# QSPI.net
KiCad netlist of a schematic drawn in Altium Designer
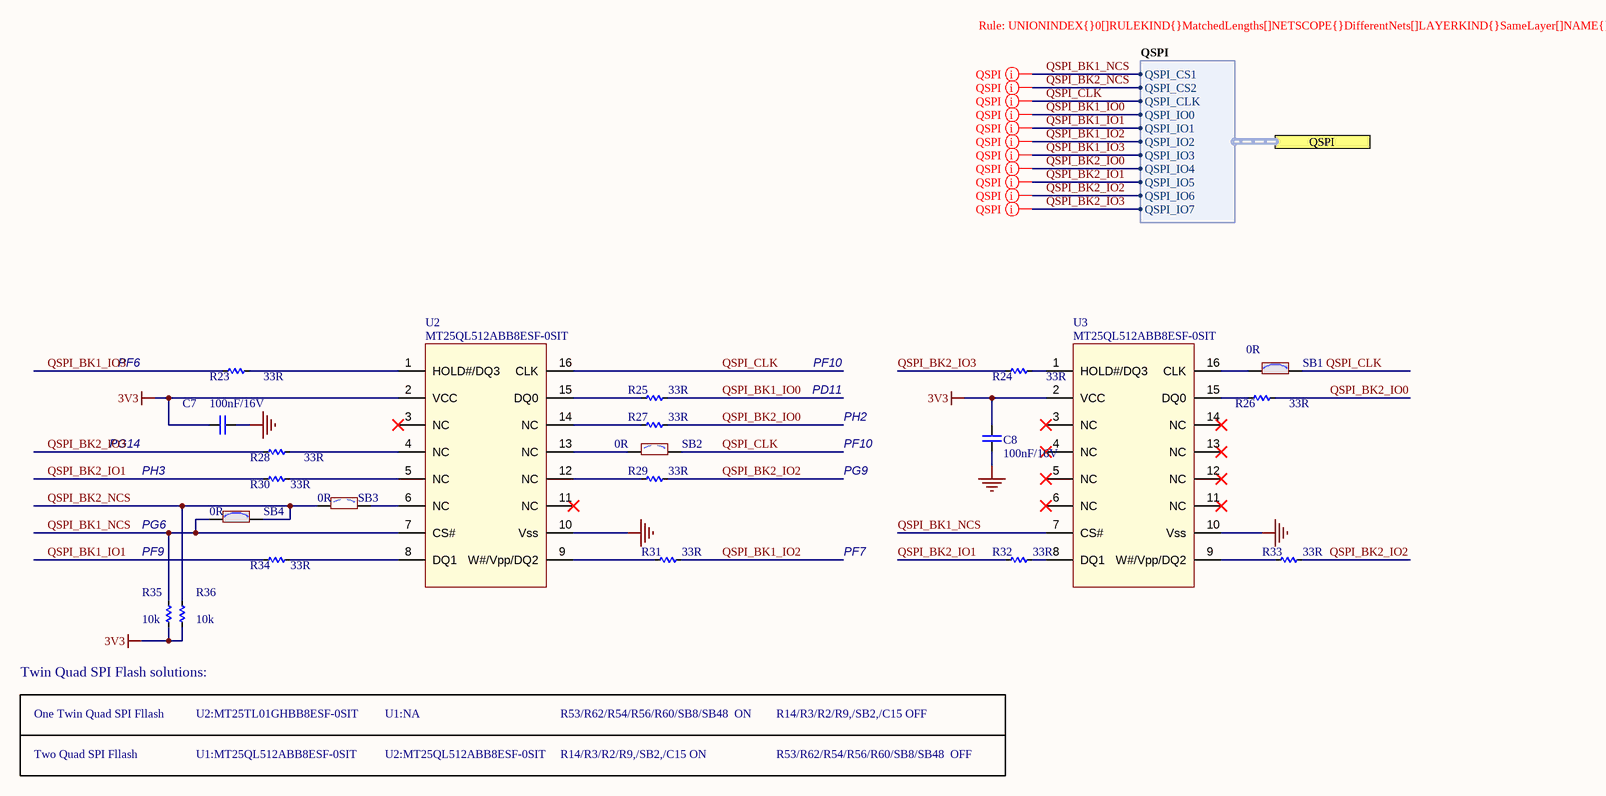
[diagram p0: QSPI.SchDoc]

(export (version "E")
  (design (tool "Eeschema 10.0.6"))
  (components
    (comp (ref "C7")
      (value "100nF/16V")
      (footprint "CAP_C_1608X80")
      (description "CAP_Chip")
      (libsource (lib "LABLIB") (part "CAP_SMD"))
    )
    (comp (ref "C8")
      (value "100nF/16V")
      (footprint "CAP_C_1608X80")
      (description "CAP_Chip")
      (libsource (lib "LABLIB") (part "CAP_SMD"))
    )
    (comp (ref "R23")
      (value "33R")
      (footprint "RES_C_1608X60")
      (description "RES")
      (libsource (lib "LABLIB") (part "_RES_B_2"))
    )
    (comp (ref "R24")
      (value "33R")
      (footprint "RES_C_1608X60")
      (description "RES")
      (libsource (lib "LABLIB") (part "_RES_B_2"))
    )
    (comp (ref "R25")
      (value "33R")
      (footprint "RES_C_1608X60")
      (description "RES")
      (libsource (lib "LABLIB") (part "_RES_B_2"))
    )
    (comp (ref "R26")
      (value "33R")
      (footprint "RES_C_1608X60")
      (description "RES")
      (libsource (lib "LABLIB") (part "_RES_B_2"))
    )
    (comp (ref "R27")
      (value "33R")
      (footprint "RES_C_1608X60")
      (description "RES")
      (libsource (lib "LABLIB") (part "_RES_B_2"))
    )
    (comp (ref "R28")
      (value "33R")
      (footprint "RES_C_1608X60")
      (description "RES")
      (libsource (lib "LABLIB") (part "_RES_B_2"))
    )
    (comp (ref "R29")
      (value "33R")
      (footprint "RES_C_1608X60")
      (description "RES")
      (libsource (lib "LABLIB") (part "_RES_B_2"))
    )
    (comp (ref "R30")
      (value "33R")
      (footprint "RES_C_1608X60")
      (description "RES")
      (libsource (lib "LABLIB") (part "_RES_B_2"))
    )
    (comp (ref "R31")
      (value "33R")
      (footprint "RES_C_1608X60")
      (description "RES")
      (libsource (lib "LABLIB") (part "_RES_B_2"))
    )
    (comp (ref "R32")
      (value "33R")
      (footprint "RES_C_1608X60")
      (description "RES")
      (libsource (lib "LABLIB") (part "_RES_B_2"))
    )
    (comp (ref "R33")
      (value "33R")
      (footprint "RES_C_1608X60")
      (description "RES")
      (libsource (lib "LABLIB") (part "_RES_B_2"))
    )
    (comp (ref "R34")
      (value "33R")
      (footprint "RES_C_1608X60")
      (description "RES")
      (libsource (lib "LABLIB") (part "_RES_B_2"))
    )
    (comp (ref "R35")
      (value "10k")
      (footprint "RES_C_1608X60")
      (description "RES")
      (libsource (lib "LABLIB") (part "_RES_B_2"))
    )
    (comp (ref "R36")
      (value "10k")
      (footprint "RES_C_1608X60")
      (description "RES")
      (libsource (lib "LABLIB") (part "_RES_B_2"))
    )
    (comp (ref "SB1")
      (value "0R")
      (footprint "Jump2")
      (description "Solder Bridge ON")
      (fields
        (field (name "INTERNAL_PART_NUMBER") "MCD-00071")
        (field (name "MANUFACTURER") "YAGEO")
        (field (name "PROVIDED_BY") "Subcon")
      )
      (libsource (lib "MCD_PARTS_database") (part "SB_ON"))
    )
    (comp (ref "SB2")
      (value "0R")
      (footprint "Jump2")
      (description "Solder Bridge OFF")
      (fields (field (name "INTERNAL_PART_NUMBER") "MCD-00072") (field (name "MANUFACTURER") "YAGEO"))
      (libsource (lib "MCD_PARTS_database") (part "SB_OFF"))
    )
    (comp (ref "SB3")
      (value "0R")
      (footprint "Jump2")
      (description "Solder Bridge OFF")
      (fields (field (name "INTERNAL_PART_NUMBER") "MCD-00072") (field (name "MANUFACTURER") "YAGEO"))
      (libsource (lib "MCD_PARTS_database") (part "SB_OFF"))
    )
    (comp (ref "SB4")
      (value "0R")
      (footprint "Jump2")
      (description "Solder Bridge ON")
      (fields
        (field (name "INTERNAL_PART_NUMBER") "MCD-00071")
        (field (name "MANUFACTURER") "YAGEO")
        (field (name "PROVIDED_BY") "Subcon")
      )
      (libsource (lib "MCD_PARTS_database") (part "SB_ON"))
    )
    (comp (ref "U2")
      (value "MT25QL512ABB8ESF-0SIT")
      (footprint "SOP2-16_7P5X10P3_MRN")
      (description "Micron Serial NOR Flash Memory")
      (fields
        (field (name "INTERNAL_PART_NUMBER") "MCD-01128")
        (field (name "MANUFACTURER") "MICRON")
        (field (name "PROVIDED_BY") "Subcon")
      )
      (libsource (lib "MCD_PARTS_database") (part "MT25QL512ABB8ESF-0SIT"))
    )
    (comp (ref "U3")
      (value "MT25QL512ABB8ESF-0SIT")
      (footprint "SOP2-16_7P5X10P3_MRN")
      (description "Micron Serial NOR Flash Memory")
      (fields
        (field (name "INTERNAL_PART_NUMBER") "MCD-01128")
        (field (name "MANUFACTURER") "MICRON")
        (field (name "PROVIDED_BY") "Subcon")
      )
      (libsource (lib "MCD_PARTS_database") (part "MT25QL512ABB8ESF-0SIT"))
    )
  )
  (nets
    (net (code "2") (name "/QSPI_BK1_IO0") (class "Default")
      (node (ref "R25") (pin "2") (pinfunction "2_2") (pintype "passive"))
    )
    (net (code "3") (name "/QSPI_BK1_IO1") (class "Default")
      (node (ref "R34") (pin "1") (pinfunction "1_1") (pintype "passive"))
    )
    (net (code "4") (name "/QSPI_BK1_IO2") (class "Default")
      (node (ref "R31") (pin "2") (pinfunction "2_2") (pintype "passive"))
    )
    (net (code "5") (name "/QSPI_BK1_IO3") (class "Default")
      (node (ref "R23") (pin "1") (pinfunction "1_1") (pintype "passive"))
    )
    (net (code "6") (name "/QSPI_BK1_NCS") (class "Default")
      (node (ref "R35") (pin "2") (pinfunction "2_2") (pintype "passive"))
      (node (ref "SB4") (pin "1") (pinfunction "1_1") (pintype "passive"))
      (node (ref "U2") (pin "7") (pinfunction "CS#_7") (pintype "passive"))
      (node (ref "U3") (pin "7") (pinfunction "CS#_7") (pintype "passive"))
    )
    (net (code "7") (name "/QSPI_BK2_IO0") (class "Default")
      (node (ref "R26") (pin "2") (pinfunction "2_2") (pintype "passive"))
      (node (ref "R27") (pin "2") (pinfunction "2_2") (pintype "passive"))
    )
    (net (code "8") (name "/QSPI_BK2_IO1") (class "Default")
      (node (ref "R30") (pin "1") (pinfunction "1_1") (pintype "passive"))
      (node (ref "R32") (pin "1") (pinfunction "1_1") (pintype "passive"))
    )
    (net (code "9") (name "/QSPI_BK2_IO2") (class "Default")
      (node (ref "R29") (pin "2") (pinfunction "2_2") (pintype "passive"))
      (node (ref "R33") (pin "2") (pinfunction "2_2") (pintype "passive"))
    )
    (net (code "10") (name "/QSPI_BK2_IO3") (class "Default")
      (node (ref "R24") (pin "1") (pinfunction "1_1") (pintype "passive"))
      (node (ref "R28") (pin "1") (pinfunction "1_1") (pintype "passive"))
    )
    (net (code "11") (name "/QSPI_BK2_NCS") (class "Default")
      (node (ref "R36") (pin "2") (pinfunction "2_2") (pintype "passive"))
      (node (ref "SB3") (pin "1") (pinfunction "1_1") (pintype "passive"))
      (node (ref "SB4") (pin "2") (pinfunction "2_2") (pintype "passive"))
    )
    (net (code "12") (name "/QSPI_CLK") (class "Default")
      (node (ref "SB1") (pin "2") (pinfunction "2_2") (pintype "passive"))
      (node (ref "SB2") (pin "2") (pinfunction "2_2") (pintype "passive"))
      (node (ref "U2") (pin "16") (pinfunction "CLK_16") (pintype "passive"))
    )
    (net (code "14") (name "3V3") (class "Default")
      (node (ref "C7") (pin "2") (pinfunction "2_2") (pintype "passive"))
      (node (ref "C8") (pin "1") (pinfunction "1_1") (pintype "passive"))
      (node (ref "R35") (pin "1") (pinfunction "1_1") (pintype "passive"))
      (node (ref "R36") (pin "1") (pinfunction "1_1") (pintype "passive"))
      (node (ref "U2") (pin "2") (pinfunction "VCC_2") (pintype "passive"))
      (node (ref "U3") (pin "2") (pinfunction "VCC_2") (pintype "passive"))
    )
    (net (code "15") (name "GND") (class "Default")
      (node (ref "C7") (pin "1") (pinfunction "1_1") (pintype "passive"))
      (node (ref "C8") (pin "2") (pinfunction "2_2") (pintype "passive"))
      (node (ref "U2") (pin "10") (pinfunction "Vss_10") (pintype "passive"))
      (node (ref "U3") (pin "10") (pinfunction "Vss_10") (pintype "passive"))
    )
    (net (code "16") (name "Net-(R27-Pad1)") (class "Default")
      (node (ref "R27") (pin "1") (pinfunction "1_1") (pintype "passive"))
      (node (ref "U2") (pin "14") (pinfunction "NC_14") (pintype "passive"))
    )
    (net (code "17") (name "Net-(R28-Pad2)") (class "Default")
      (node (ref "R28") (pin "2") (pinfunction "2_2") (pintype "passive"))
      (node (ref "U2") (pin "4") (pinfunction "NC_4") (pintype "passive"))
    )
    (net (code "18") (name "Net-(R29-Pad1)") (class "Default")
      (node (ref "R29") (pin "1") (pinfunction "1_1") (pintype "passive"))
      (node (ref "U2") (pin "12") (pinfunction "NC_12") (pintype "passive"))
    )
    (net (code "19") (name "Net-(R30-Pad2)") (class "Default")
      (node (ref "R30") (pin "2") (pinfunction "2_2") (pintype "passive"))
      (node (ref "U2") (pin "5") (pinfunction "NC_5") (pintype "passive"))
    )
    (net (code "20") (name "Net-(SB2-Pad1)") (class "Default")
      (node (ref "SB2") (pin "1") (pinfunction "1_1") (pintype "passive"))
      (node (ref "U2") (pin "13") (pinfunction "NC_13") (pintype "passive"))
    )
    (net (code "21") (name "Net-(SB3-Pad2)") (class "Default")
      (node (ref "SB3") (pin "2") (pinfunction "2_2") (pintype "passive"))
      (node (ref "U2") (pin "6") (pinfunction "NC_6") (pintype "passive"))
    )
    (net (code "22") (name "Net-(U2-DQ0)") (class "Default")
      (node (ref "R25") (pin "1") (pinfunction "1_1") (pintype "passive"))
      (node (ref "U2") (pin "15") (pinfunction "DQ0_15") (pintype "passive"))
    )
    (net (code "23") (name "Net-(U2-DQ1)") (class "Default")
      (node (ref "R34") (pin "2") (pinfunction "2_2") (pintype "passive"))
      (node (ref "U2") (pin "8") (pinfunction "DQ1_8") (pintype "passive"))
    )
    (net (code "24") (name "Net-(U2-HOLD#{slash}DQ3)") (class "Default")
      (node (ref "R23") (pin "2") (pinfunction "2_2") (pintype "passive"))
      (node (ref "U2") (pin "1") (pinfunction "HOLD#/DQ3_1") (pintype "passive"))
    )
    (net (code "25") (name "Net-(U2-W#{slash}Vpp{slash}DQ2)") (class "Default")
      (node (ref "R31") (pin "1") (pinfunction "1_1") (pintype "passive"))
      (node (ref "U2") (pin "9") (pinfunction "W#/Vpp/DQ2_9") (pintype "passive"))
    )
    (net (code "26") (name "Net-(U3-CLK)") (class "Default")
      (node (ref "SB1") (pin "1") (pinfunction "1_1") (pintype "passive"))
      (node (ref "U3") (pin "16") (pinfunction "CLK_16") (pintype "passive"))
    )
    (net (code "27") (name "Net-(U3-DQ0)") (class "Default")
      (node (ref "R26") (pin "1") (pinfunction "1_1") (pintype "passive"))
      (node (ref "U3") (pin "15") (pinfunction "DQ0_15") (pintype "passive"))
    )
    (net (code "28") (name "Net-(U3-DQ1)") (class "Default")
      (node (ref "R32") (pin "2") (pinfunction "2_2") (pintype "passive"))
      (node (ref "U3") (pin "8") (pinfunction "DQ1_8") (pintype "passive"))
    )
    (net (code "29") (name "Net-(U3-HOLD#{slash}DQ3)") (class "Default")
      (node (ref "R24") (pin "2") (pinfunction "2_2") (pintype "passive"))
      (node (ref "U3") (pin "1") (pinfunction "HOLD#/DQ3_1") (pintype "passive"))
    )
    (net (code "30") (name "Net-(U3-W#{slash}Vpp{slash}DQ2)") (class "Default")
      (node (ref "R33") (pin "1") (pinfunction "1_1") (pintype "passive"))
      (node (ref "U3") (pin "9") (pinfunction "W#/Vpp/DQ2_9") (pintype "passive"))
    )
    (net (code "31") (name "unconnected-(U2-NC-Pad3)") (class "Default")
      (node (ref "U2") (pin "3") (pinfunction "NC_3") (pintype "passive+no_connect"))
    )
    (net (code "32") (name "unconnected-(U2-NC-Pad11)") (class "Default")
      (node (ref "U2") (pin "11") (pinfunction "NC_11") (pintype "passive+no_connect"))
    )
    (net (code "33") (name "unconnected-(U3-NC-Pad3)") (class "Default")
      (node (ref "U3") (pin "3") (pinfunction "NC_3") (pintype "passive+no_connect"))
    )
    (net (code "34") (name "unconnected-(U3-NC-Pad4)") (class "Default")
      (node (ref "U3") (pin "4") (pinfunction "NC_4") (pintype "passive+no_connect"))
    )
    (net (code "35") (name "unconnected-(U3-NC-Pad5)") (class "Default")
      (node (ref "U3") (pin "5") (pinfunction "NC_5") (pintype "passive+no_connect"))
    )
    (net (code "36") (name "unconnected-(U3-NC-Pad6)") (class "Default")
      (node (ref "U3") (pin "6") (pinfunction "NC_6") (pintype "passive+no_connect"))
    )
    (net (code "37") (name "unconnected-(U3-NC-Pad11)") (class "Default")
      (node (ref "U3") (pin "11") (pinfunction "NC_11") (pintype "passive+no_connect"))
    )
    (net (code "38") (name "unconnected-(U3-NC-Pad12)") (class "Default")
      (node (ref "U3") (pin "12") (pinfunction "NC_12") (pintype "passive+no_connect"))
    )
    (net (code "39") (name "unconnected-(U3-NC-Pad13)") (class "Default")
      (node (ref "U3") (pin "13") (pinfunction "NC_13") (pintype "passive+no_connect"))
    )
    (net (code "40") (name "unconnected-(U3-NC-Pad14)") (class "Default")
      (node (ref "U3") (pin "14") (pinfunction "NC_14") (pintype "passive+no_connect"))
    )
  )
)
